# sch.net
KiCad netlist of a schematic drawn in EasyEDA
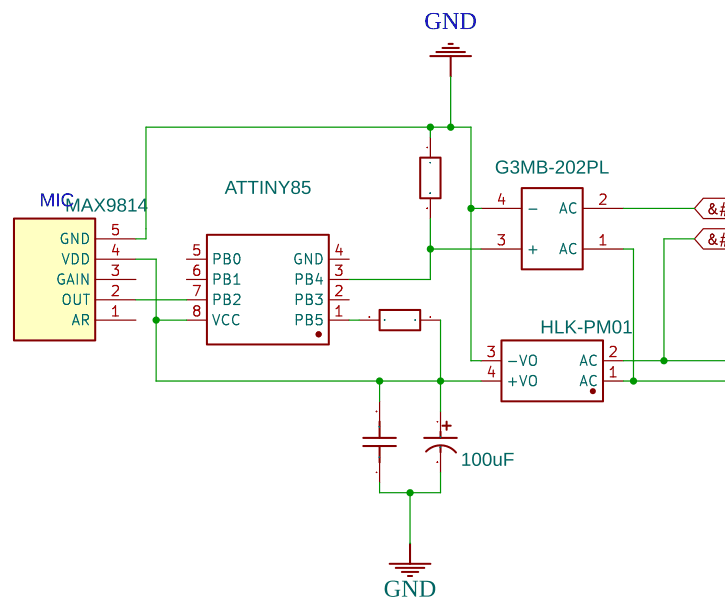
[diagram p0: schematic sheet]

(export (version "E")
  (design (tool "Eeschema 10.0.6"))
  (components
    (comp (ref "C3")
      (value "100nF")
      (fields
        (field (name "Manufacturer Part") "RDER71E104K0M1H03A")
        (field (name "Manufacturer") "muRata(村田)")
      )
      (libsource (lib "") (part "RDER71E104K0M1H03A"))
    )
    (comp (ref "C4")
      (value "100uF")
      (fields (field (name "Manufacturer Part") "KF101M016C110A") (field (name "Manufacturer") "CapXon"))
      (libsource (lib "") (part "KF101M016C110A"))
    )
    (comp (ref "K2")
      (value "G3MB-202PL")
      (fields (field (name "Manufacturer") "OMRON"))
      (libsource (lib "") (part "G3MB-202PL"))
    )
    (comp (ref "R3")
      (value "10k")
      (fields
        (field (name "Manufacturer Part") "MF1/4W-470KΩ±1%T52")
        (field (name "Manufacturer") "Huaxing Mechanical-Elec.")
      )
      (libsource (lib "") (part "MF1/4W-470KΩ±1%T52"))
    )
    (comp (ref "R4")
      (value "10k")
      (fields
        (field (name "Manufacturer Part") "MF1/4W-470KΩ±1%T52")
        (field (name "Manufacturer") "Huaxing Mechanical-Elec.")
      )
      (libsource (lib "") (part "MF1/4W-470KΩ±1%T52_1"))
    )
    (comp (ref "U4") (value "MAX9814") (libsource (lib "") (part "MAX9814 MODULE")))
    (comp (ref "U6")
      (value "HLK-PM01")
      (fields (field (name "Manufacturer") "HI-LINK"))
      (libsource (lib "") (part "HLK-PM01"))
    )
    (comp (ref "U7")
      (value "ATTINY85")
      (fields
        (field (name "Manufacturer Part") "ATTINY85V-10SUR")
        (field (name "Manufacturer") "MICROCHIP(美国微芯)")
      )
      (libsource (lib "") (part "ATTINY85V-10SUR"))
    )
  )
  (nets
    (net (code "1") (name "&#126;220V-0") (class "Default")
      (node (ref "U6") (pin "2") (pinfunction "AC_2") (pintype "unspecified"))
    )
    (net (code "2") (name "&#126;220V-1") (class "Default")
      (node (ref "K2") (pin "1") (pinfunction "AC_1") (pintype "unspecified"))
      (node (ref "U6") (pin "1") (pinfunction "AC_1") (pintype "unspecified"))
    )
    (net (code "3") (name "&#126;LOAD0") (class "Default")
      (node (ref "K2") (pin "2") (pinfunction "AC_2") (pintype "unspecified"))
    )
    (net (code "4") (name "GND") (class "Default")
      (node (ref "C3") (pin "1") (pinfunction "1_1") (pintype "unspecified"))
      (node (ref "C4") (pin "2") (pinfunction "2_2") (pintype "input"))
      (node (ref "K2") (pin "4") (pinfunction "-_4") (pintype "unspecified"))
      (node (ref "R3") (pin "1") (pinfunction "1_1") (pintype "unspecified"))
      (node (ref "U4") (pin "5") (pinfunction "GND_5") (pintype "unspecified"))
      (node (ref "U6") (pin "3") (pinfunction "-VO_3") (pintype "unspecified"))
    )
    (net (code "5") (name "Net-(K2-+)") (class "Default")
      (node (ref "K2") (pin "3") (pinfunction "+_3") (pintype "unspecified"))
      (node (ref "R3") (pin "2") (pinfunction "2_2") (pintype "unspecified"))
      (node (ref "U7") (pin "3") (pinfunction "PB4_3") (pintype "unspecified"))
    )
    (net (code "6") (name "Net-(U4-OUT)") (class "Default")
      (node (ref "U4") (pin "2") (pinfunction "OUT_2") (pintype "unspecified"))
      (node (ref "U7") (pin "7") (pinfunction "PB2_7") (pintype "unspecified"))
    )
    (net (code "7") (name "Net-(U4-VDD)") (class "Default")
      (node (ref "C3") (pin "2") (pinfunction "2_2") (pintype "unspecified"))
      (node (ref "C4") (pin "1") (pinfunction "1_1") (pintype "input"))
      (node (ref "R4") (pin "1") (pinfunction "1_1") (pintype "unspecified"))
      (node (ref "U4") (pin "4") (pinfunction "VDD_4") (pintype "unspecified"))
      (node (ref "U6") (pin "4") (pinfunction "+VO_4") (pintype "unspecified"))
      (node (ref "U7") (pin "8") (pinfunction "VCC_8") (pintype "unspecified"))
    )
    (net (code "8") (name "Net-(U7-PB5)") (class "Default")
      (node (ref "R4") (pin "2") (pinfunction "2_2") (pintype "unspecified"))
      (node (ref "U7") (pin "1") (pinfunction "PB5_1") (pintype "unspecified"))
    )
    (net (code "9") (name "unconnected-(U4-AR-Pad1)") (class "Default")
      (node (ref "U4") (pin "1") (pinfunction "AR_1") (pintype "unspecified"))
    )
    (net (code "10") (name "unconnected-(U4-GAIN-Pad3)") (class "Default")
      (node (ref "U4") (pin "3") (pinfunction "GAIN_3") (pintype "unspecified"))
    )
    (net (code "11") (name "unconnected-(U7-GND-Pad4)") (class "Default")
      (node (ref "U7") (pin "4") (pinfunction "GND_4") (pintype "unspecified"))
    )
    (net (code "12") (name "unconnected-(U7-PB0-Pad5)") (class "Default")
      (node (ref "U7") (pin "5") (pinfunction "PB0_5") (pintype "unspecified"))
    )
    (net (code "13") (name "unconnected-(U7-PB1-Pad6)") (class "Default")
      (node (ref "U7") (pin "6") (pinfunction "PB1_6") (pintype "unspecified"))
    )
    (net (code "14") (name "unconnected-(U7-PB3-Pad2)") (class "Default")
      (node (ref "U7") (pin "2") (pinfunction "PB3_2") (pintype "unspecified"))
    )
  )
)
